# motor_controller.net
KiCad netlist of a schematic drawn in Altium Designer
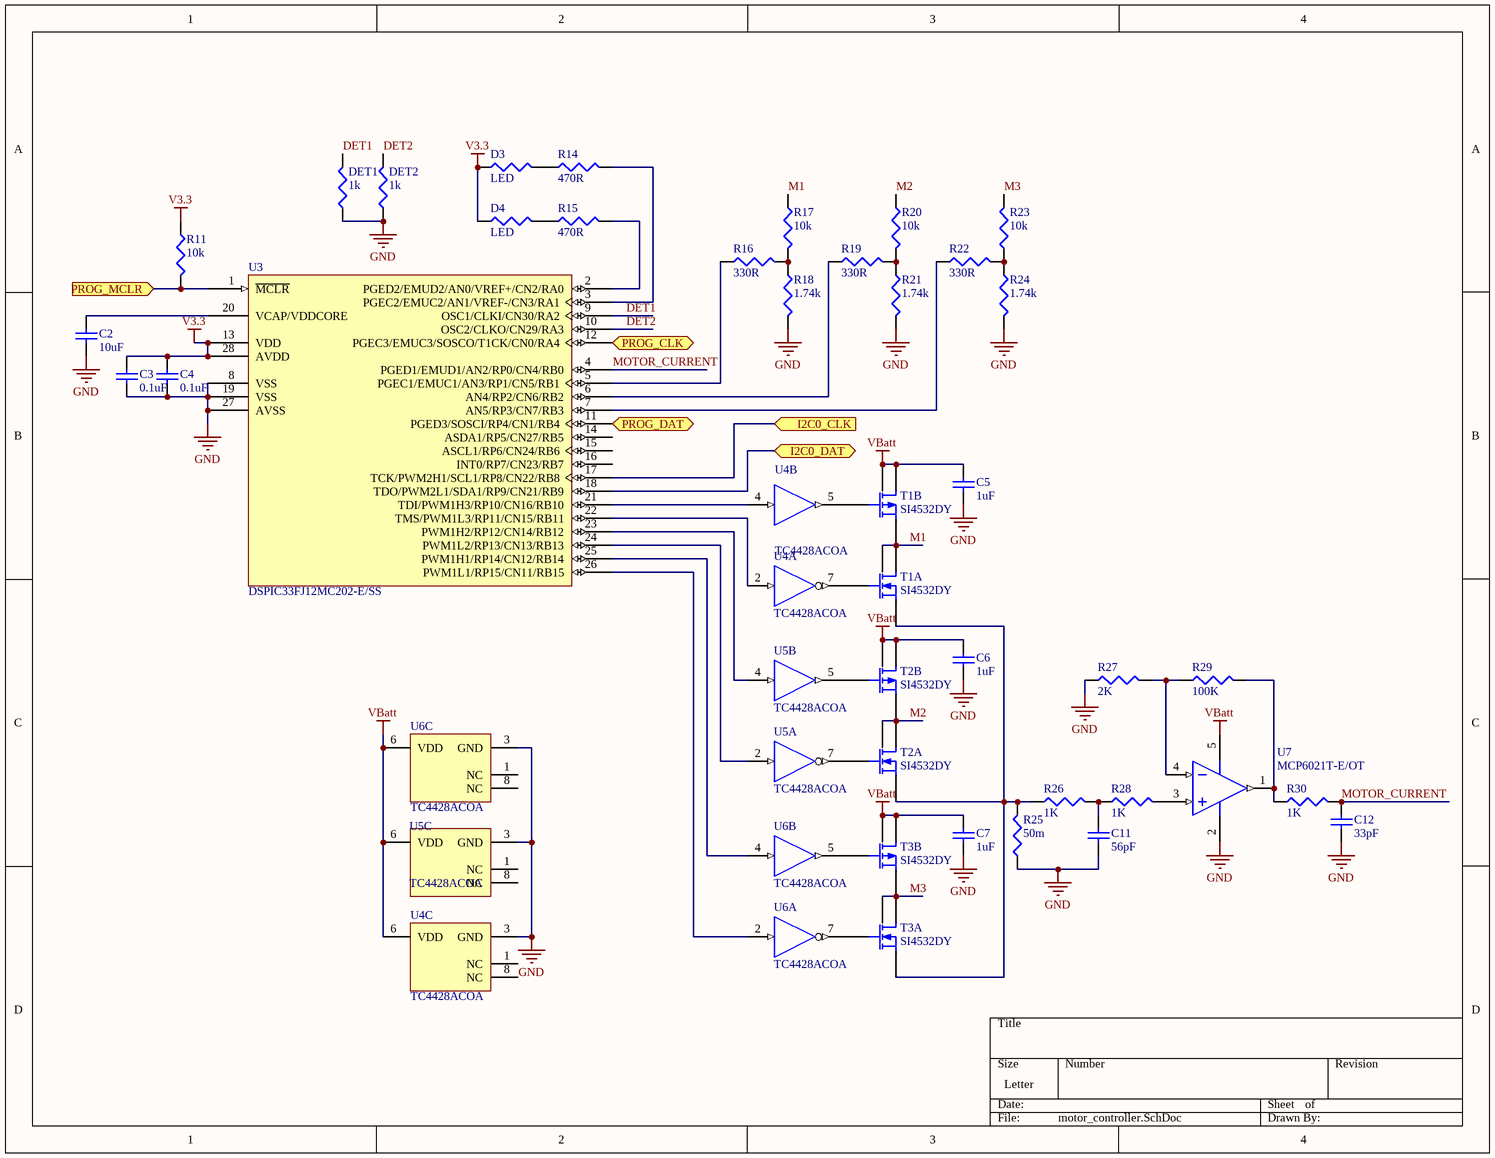
[diagram p0: motor_controller.SchDoc]

(export (version "E")
  (design (tool "Eeschema 10.0.6"))
  (components
    (comp (ref "C2")
      (value "10uF")
      (footprint "1608[0603]")
      (description "Capacitor (Semiconductor SIM Model)")
      (fields (field (name "PUBLISHER") "Altium Limited"))
      (libsource (lib "Miscellaneous Devices") (part "Cap Semi"))
    )
    (comp (ref "C3")
      (value "0.1uF")
      (footprint "1608[0603]")
      (description "Capacitor (Semiconductor SIM Model)")
      (fields (field (name "PUBLISHER") "Altium Limited"))
      (libsource (lib "Miscellaneous Devices") (part "Cap Semi"))
    )
    (comp (ref "C4")
      (value "0.1uF")
      (footprint "1608[0603]")
      (description "Capacitor (Semiconductor SIM Model)")
      (fields (field (name "PUBLISHER") "Altium Limited"))
      (libsource (lib "Miscellaneous Devices") (part "Cap Semi"))
    )
    (comp (ref "C5")
      (value "1uF")
      (footprint "1608[0603]")
      (description "Capacitor (Semiconductor SIM Model)")
      (fields (field (name "PUBLISHER") "Altium Limited"))
      (libsource (lib "Miscellaneous Devices") (part "Cap Semi"))
    )
    (comp (ref "C6")
      (value "1uF")
      (footprint "1608[0603]")
      (description "Capacitor (Semiconductor SIM Model)")
      (fields (field (name "PUBLISHER") "Altium Limited"))
      (libsource (lib "Miscellaneous Devices") (part "Cap Semi"))
    )
    (comp (ref "C7")
      (value "1uF")
      (footprint "1608[0603]")
      (description "Capacitor (Semiconductor SIM Model)")
      (fields (field (name "PUBLISHER") "Altium Limited"))
      (libsource (lib "Miscellaneous Devices") (part "Cap Semi"))
    )
    (comp (ref "C11")
      (value "56pF")
      (footprint "1608[0603]")
      (description "Capacitor (Semiconductor SIM Model)")
      (fields (field (name "PUBLISHER") "Altium Limited"))
      (libsource (lib "Miscellaneous Devices") (part "Cap Semi"))
    )
    (comp (ref "C12")
      (value "33pF")
      (footprint "1608[0603]")
      (description "Capacitor (Semiconductor SIM Model)")
      (fields (field (name "PUBLISHER") "Altium Limited"))
      (libsource (lib "Miscellaneous Devices") (part "Cap Semi"))
    )
    (comp (ref "D3")
      (value "LED")
      (footprint "J1-0603")
      (description "Resistor")
      (fields (field (name "PUBLISHER") "Altium Limited"))
      (libsource (lib "Miscellaneous Devices") (part "Res3"))
    )
    (comp (ref "D4")
      (value "LED")
      (footprint "J1-0603")
      (description "Resistor")
      (fields (field (name "PUBLISHER") "Altium Limited"))
      (libsource (lib "Miscellaneous Devices") (part "Res3"))
    )
    (comp (ref "DET1")
      (value "1k")
      (footprint "J1-0603")
      (description "Resistor")
      (fields (field (name "PUBLISHER") "Altium Limited"))
      (libsource (lib "Miscellaneous Devices") (part "Res3"))
    )
    (comp (ref "DET2")
      (value "1k")
      (footprint "J1-0603")
      (description "Resistor")
      (fields (field (name "PUBLISHER") "Altium Limited"))
      (libsource (lib "Miscellaneous Devices") (part "Res3"))
    )
    (comp (ref "R11")
      (value "10k")
      (footprint "J1-0603")
      (description "Resistor")
      (fields (field (name "PUBLISHER") "Altium Limited"))
      (libsource (lib "Miscellaneous Devices") (part "Res3"))
    )
    (comp (ref "R14")
      (value "470R")
      (footprint "J1-0603")
      (description "Resistor")
      (fields (field (name "PUBLISHER") "Altium Limited"))
      (libsource (lib "Miscellaneous Devices") (part "Res3"))
    )
    (comp (ref "R15")
      (value "470R")
      (footprint "J1-0603")
      (description "Resistor")
      (fields (field (name "PUBLISHER") "Altium Limited"))
      (libsource (lib "Miscellaneous Devices") (part "Res3"))
    )
    (comp (ref "R16")
      (value "330R")
      (footprint "J1-0603")
      (description "Resistor")
      (fields (field (name "PUBLISHER") "Altium Limited"))
      (libsource (lib "Miscellaneous Devices") (part "Res3"))
    )
    (comp (ref "R17")
      (value "10k")
      (footprint "J1-0603")
      (description "Resistor")
      (fields (field (name "PUBLISHER") "Altium Limited"))
      (libsource (lib "Miscellaneous Devices") (part "Res3"))
    )
    (comp (ref "R18")
      (value "1.74k")
      (footprint "J1-0603")
      (description "Resistor")
      (fields (field (name "PUBLISHER") "Altium Limited"))
      (libsource (lib "Miscellaneous Devices") (part "Res3"))
    )
    (comp (ref "R19")
      (value "330R")
      (footprint "J1-0603")
      (description "Resistor")
      (fields (field (name "PUBLISHER") "Altium Limited"))
      (libsource (lib "Miscellaneous Devices") (part "Res3"))
    )
    (comp (ref "R20")
      (value "10k")
      (footprint "J1-0603")
      (description "Resistor")
      (fields (field (name "PUBLISHER") "Altium Limited"))
      (libsource (lib "Miscellaneous Devices") (part "Res3"))
    )
    (comp (ref "R21")
      (value "1.74k")
      (footprint "J1-0603")
      (description "Resistor")
      (fields (field (name "PUBLISHER") "Altium Limited"))
      (libsource (lib "Miscellaneous Devices") (part "Res3"))
    )
    (comp (ref "R22")
      (value "330R")
      (footprint "J1-0603")
      (description "Resistor")
      (fields (field (name "PUBLISHER") "Altium Limited"))
      (libsource (lib "Miscellaneous Devices") (part "Res3"))
    )
    (comp (ref "R23")
      (value "10k")
      (footprint "J1-0603")
      (description "Resistor")
      (fields (field (name "PUBLISHER") "Altium Limited"))
      (libsource (lib "Miscellaneous Devices") (part "Res3"))
    )
    (comp (ref "R24")
      (value "1.74k")
      (footprint "J1-0603")
      (description "Resistor")
      (fields (field (name "PUBLISHER") "Altium Limited"))
      (libsource (lib "Miscellaneous Devices") (part "Res3"))
    )
    (comp (ref "R25")
      (value "50m")
      (footprint "14-1210")
      (description "Resistor")
      (fields (field (name "PUBLISHER") "Altium Limited"))
      (libsource (lib "Miscellaneous Devices") (part "Res3"))
    )
    (comp (ref "R26")
      (value "1K")
      (footprint "J1-0603")
      (description "Resistor")
      (fields (field (name "PUBLISHER") "Altium Limited"))
      (libsource (lib "Miscellaneous Devices") (part "Res3"))
    )
    (comp (ref "R27")
      (value "2K")
      (footprint "J1-0603")
      (description "Resistor")
      (fields (field (name "PUBLISHER") "Altium Limited"))
      (libsource (lib "Miscellaneous Devices") (part "Res3"))
    )
    (comp (ref "R28")
      (value "1K")
      (footprint "J1-0603")
      (description "Resistor")
      (fields (field (name "PUBLISHER") "Altium Limited"))
      (libsource (lib "Miscellaneous Devices") (part "Res3"))
    )
    (comp (ref "R29")
      (value "100K")
      (footprint "J1-0603")
      (description "Resistor")
      (fields (field (name "PUBLISHER") "Altium Limited"))
      (libsource (lib "Miscellaneous Devices") (part "Res3"))
    )
    (comp (ref "R30")
      (value "1K")
      (footprint "J1-0603")
      (description "Resistor")
      (fields (field (name "PUBLISHER") "Altium Limited"))
      (libsource (lib "Miscellaneous Devices") (part "Res3"))
    )
    (comp (ref "T1")
      (value "SI4532DY")
      (footprint "SOIC127P600-8L")
      (libsource (lib "custom_for_quadrotor") (part "SI4532DY"))
    )
    (comp (ref "T2")
      (value "SI4532DY")
      (footprint "SOIC127P600-8L")
      (libsource (lib "custom_for_quadrotor") (part "SI4532DY"))
    )
    (comp (ref "T3")
      (value "SI4532DY")
      (footprint "SOIC127P600-8L")
      (libsource (lib "custom_for_quadrotor") (part "SI4532DY"))
    )
    (comp (ref "U3")
      (value "DSPIC33FJ12MC202-E/SS")
      (footprint "SSOP-SS28_N")
      (libsource (lib "Microchip dsPIC33F") (part "DSPIC33FJ12MC202-E/SS"))
    )
    (comp (ref "U4")
      (value "TC4428ACOA")
      (footprint "SOIC-OA8_N")
      (description "1.5A Dual High-Speed Power MOSFET Driver, Complementary, Commercial Temperature")
      (libsource (lib "Microchip Power Management MOSFET Driver") (part "TC4428ACOA"))
    )
    (comp (ref "U5")
      (value "TC4428ACOA")
      (footprint "SOIC-OA8_N")
      (description "1.5A Dual High-Speed Power MOSFET Driver, Complementary, Commercial Temperature")
      (libsource (lib "Microchip Power Management MOSFET Driver") (part "TC4428ACOA"))
    )
    (comp (ref "U6")
      (value "TC4428ACOA")
      (footprint "SOIC-OA8_N")
      (description "1.5A Dual High-Speed Power MOSFET Driver, Complementary, Commercial Temperature")
      (libsource (lib "Microchip Power Management MOSFET Driver") (part "TC4428ACOA"))
    )
    (comp (ref "U7")
      (value "MCP6021T-E/OT")
      (footprint "SOT-23-OT5_N")
      (libsource (lib "Microchip Linear") (part "MCP6021T-E/OT"))
    )
  )
  (nets
    (net (code "1") (name "/DET1") (class "Default")
      (node (ref "DET1") (pin "2") (pinfunction "2_2") (pintype "passive"))
      (node (ref "U3") (pin "9") (pinfunction "OSC1/CLKI/CN30/RA2_9") (pintype "bidirectional"))
    )
    (net (code "2") (name "/DET2") (class "Default")
      (node (ref "DET2") (pin "2") (pinfunction "2_2") (pintype "passive"))
      (node (ref "U3") (pin "10") (pinfunction "OSC2/CLKO/CN29/RA3_10") (pintype "bidirectional"))
    )
    (net (code "3") (name "/I2C0_CLK") (class "Default")
      (node (ref "U3") (pin "17") (pinfunction "TCK/PWM2H1/SCL1/RP8/CN22/RB8_17") (pintype "bidirectional"))
    )
    (net (code "4") (name "/I2C0_DAT") (class "Default")
      (node (ref "U3") (pin "18") (pinfunction "TDO/PWM2L1/SDA1/RP9/CN21/RB9_18") (pintype "bidirectional"))
    )
    (net (code "5") (name "/M1") (class "Default")
      (node (ref "R17") (pin "1") (pinfunction "1_1") (pintype "passive"))
      (node (ref "T1") (pin "3") (pinfunction "S2_3") (pintype "passive"))
      (node (ref "T1") (pin "7") (pinfunction "D1_7") (pintype "passive"))
      (node (ref "T1") (pin "8") (pinfunction "D1_8") (pintype "passive"))
    )
    (net (code "6") (name "/M2") (class "Default")
      (node (ref "R20") (pin "1") (pinfunction "1_1") (pintype "passive"))
      (node (ref "T2") (pin "3") (pinfunction "S2_3") (pintype "passive"))
      (node (ref "T2") (pin "7") (pinfunction "D1_7") (pintype "passive"))
      (node (ref "T2") (pin "8") (pinfunction "D1_8") (pintype "passive"))
    )
    (net (code "7") (name "/M3") (class "Default")
      (node (ref "R23") (pin "2") (pinfunction "2_2") (pintype "passive"))
      (node (ref "T3") (pin "3") (pinfunction "S2_3") (pintype "passive"))
      (node (ref "T3") (pin "7") (pinfunction "D1_7") (pintype "passive"))
      (node (ref "T3") (pin "8") (pinfunction "D1_8") (pintype "passive"))
    )
    (net (code "8") (name "/MOTOR_CURRENT") (class "Default")
      (node (ref "C12") (pin "2") (pinfunction "2_2") (pintype "passive"))
      (node (ref "R30") (pin "2") (pinfunction "2_2") (pintype "passive"))
      (node (ref "U3") (pin "4") (pinfunction "PGED1/EMUD1/AN2/RP0/CN4/RB0_4") (pintype "bidirectional"))
    )
    (net (code "9") (name "/PROG_CLK") (class "Default")
      (node (ref "U3") (pin "12") (pinfunction "PGEC3/EMUC3/SOSCO/T1CK/CN0/RA4_12") (pintype "bidirectional"))
    )
    (net (code "10") (name "/PROG_DAT") (class "Default")
      (node (ref "U3") (pin "11") (pinfunction "PGED3/SOSCI/RP4/CN1/RB4_11") (pintype "bidirectional"))
    )
    (net (code "11") (name "/PROG_MCLR") (class "Default")
      (node (ref "R11") (pin "2") (pinfunction "2_2") (pintype "passive"))
      (node (ref "U3") (pin "1") (pinfunction "~{MCLR}_1") (pintype "input"))
    )
    (net (code "12") (name "GND") (class "Default")
      (node (ref "C11") (pin "1") (pinfunction "1_1") (pintype "passive"))
      (node (ref "C12") (pin "1") (pinfunction "1_1") (pintype "passive"))
      (node (ref "C2") (pin "1") (pinfunction "1_1") (pintype "passive"))
      (node (ref "C3") (pin "1") (pinfunction "1_1") (pintype "passive"))
      (node (ref "C4") (pin "1") (pinfunction "1_1") (pintype "passive"))
      (node (ref "C5") (pin "1") (pinfunction "1_1") (pintype "passive"))
      (node (ref "C6") (pin "1") (pinfunction "1_1") (pintype "passive"))
      (node (ref "C7") (pin "1") (pinfunction "1_1") (pintype "passive"))
      (node (ref "DET1") (pin "1") (pinfunction "1_1") (pintype "passive"))
      (node (ref "DET2") (pin "1") (pinfunction "1_1") (pintype "passive"))
      (node (ref "R18") (pin "2") (pinfunction "2_2") (pintype "passive"))
      (node (ref "R21") (pin "2") (pinfunction "2_2") (pintype "passive"))
      (node (ref "R24") (pin "2") (pinfunction "2_2") (pintype "passive"))
      (node (ref "R25") (pin "1") (pinfunction "1_1") (pintype "passive"))
      (node (ref "R27") (pin "1") (pinfunction "1_1") (pintype "passive"))
      (node (ref "U3") (pin "19") (pinfunction "VSS_19") (pintype "power_in"))
      (node (ref "U3") (pin "27") (pinfunction "AVSS_27") (pintype "power_in"))
      (node (ref "U3") (pin "8") (pinfunction "VSS_8") (pintype "power_in"))
      (node (ref "U4") (pin "3") (pinfunction "GND_3") (pintype "power_in"))
      (node (ref "U5") (pin "3") (pinfunction "GND_3") (pintype "power_in"))
      (node (ref "U6") (pin "3") (pinfunction "GND_3") (pintype "power_in"))
      (node (ref "U7") (pin "2") (pinfunction "VSS_2") (pintype "power_in"))
    )
    (net (code "13") (name "Net-(C11-Pad2)") (class "Default")
      (node (ref "C11") (pin "2") (pinfunction "2_2") (pintype "passive"))
      (node (ref "R26") (pin "2") (pinfunction "2_2") (pintype "passive"))
      (node (ref "R28") (pin "1") (pinfunction "1_1") (pintype "passive"))
    )
    (net (code "14") (name "Net-(D3-Pad2)") (class "Default")
      (node (ref "D3") (pin "2") (pinfunction "2_2") (pintype "passive"))
      (node (ref "R14") (pin "1") (pinfunction "1_1") (pintype "passive"))
    )
    (net (code "15") (name "Net-(D4-Pad2)") (class "Default")
      (node (ref "D4") (pin "2") (pinfunction "2_2") (pintype "passive"))
      (node (ref "R15") (pin "1") (pinfunction "1_1") (pintype "passive"))
    )
    (net (code "16") (name "Net-(R16-Pad2)") (class "Default")
      (node (ref "R16") (pin "2") (pinfunction "2_2") (pintype "passive"))
      (node (ref "R17") (pin "2") (pinfunction "2_2") (pintype "passive"))
      (node (ref "R18") (pin "1") (pinfunction "1_1") (pintype "passive"))
    )
    (net (code "17") (name "Net-(R19-Pad2)") (class "Default")
      (node (ref "R19") (pin "2") (pinfunction "2_2") (pintype "passive"))
      (node (ref "R20") (pin "2") (pinfunction "2_2") (pintype "passive"))
      (node (ref "R21") (pin "1") (pinfunction "1_1") (pintype "passive"))
    )
    (net (code "18") (name "Net-(R22-Pad2)") (class "Default")
      (node (ref "R22") (pin "2") (pinfunction "2_2") (pintype "passive"))
      (node (ref "R23") (pin "1") (pinfunction "1_1") (pintype "passive"))
      (node (ref "R24") (pin "1") (pinfunction "1_1") (pintype "passive"))
    )
    (net (code "19") (name "Net-(T1A-G1)") (class "Default")
      (node (ref "T1") (pin "2") (pinfunction "G1_2") (pintype "passive"))
      (node (ref "U4") (pin "7") (pinfunction "~{OUTA}_7") (pintype "output"))
    )
    (net (code "20") (name "Net-(T1A-S1)") (class "Default")
      (node (ref "R25") (pin "2") (pinfunction "2_2") (pintype "passive"))
      (node (ref "R26") (pin "1") (pinfunction "1_1") (pintype "passive"))
      (node (ref "T1") (pin "1") (pinfunction "S1_1") (pintype "passive"))
      (node (ref "T2") (pin "1") (pinfunction "S1_1") (pintype "passive"))
      (node (ref "T3") (pin "1") (pinfunction "S1_1") (pintype "passive"))
    )
    (net (code "21") (name "Net-(T1B-G2)") (class "Default")
      (node (ref "T1") (pin "4") (pinfunction "G2_4") (pintype "passive"))
      (node (ref "U4") (pin "5") (pinfunction "OUTB_5") (pintype "output"))
    )
    (net (code "22") (name "Net-(T2A-G1)") (class "Default")
      (node (ref "T2") (pin "2") (pinfunction "G1_2") (pintype "passive"))
      (node (ref "U5") (pin "7") (pinfunction "~{OUTA}_7") (pintype "output"))
    )
    (net (code "23") (name "Net-(T2B-G2)") (class "Default")
      (node (ref "T2") (pin "4") (pinfunction "G2_4") (pintype "passive"))
      (node (ref "U5") (pin "5") (pinfunction "OUTB_5") (pintype "output"))
    )
    (net (code "24") (name "Net-(T3A-G1)") (class "Default")
      (node (ref "T3") (pin "2") (pinfunction "G1_2") (pintype "passive"))
      (node (ref "U6") (pin "7") (pinfunction "~{OUTA}_7") (pintype "output"))
    )
    (net (code "25") (name "Net-(T3B-G2)") (class "Default")
      (node (ref "T3") (pin "4") (pinfunction "G2_4") (pintype "passive"))
      (node (ref "U6") (pin "5") (pinfunction "OUTB_5") (pintype "output"))
    )
    (net (code "26") (name "Net-(U3-AN4{slash}RP2{slash}CN6{slash}RB2)") (class "Default")
      (node (ref "R19") (pin "1") (pinfunction "1_1") (pintype "passive"))
      (node (ref "U3") (pin "6") (pinfunction "AN4/RP2/CN6/RB2_6") (pintype "bidirectional"))
    )
    (net (code "27") (name "Net-(U3-AN5{slash}RP3{slash}CN7{slash}RB3)") (class "Default")
      (node (ref "R22") (pin "1") (pinfunction "1_1") (pintype "passive"))
      (node (ref "U3") (pin "7") (pinfunction "AN5/RP3/CN7/RB3_7") (pintype "bidirectional"))
    )
    (net (code "28") (name "Net-(U3-PGEC1{slash}EMUC1{slash}AN3{slash}RP1{slash}CN5{slash}RB1)") (class "Default")
      (node (ref "R16") (pin "1") (pinfunction "1_1") (pintype "passive"))
      (node (ref "U3") (pin "5") (pinfunction "PGEC1/EMUC1/AN3/RP1/CN5/RB1_5") (pintype "bidirectional"))
    )
    (net (code "29") (name "Net-(U3-PGEC2{slash}EMUC2{slash}AN1{slash}VREF-{slash}CN3{slash}RA1)") (class "Default")
      (node (ref "R14") (pin "2") (pinfunction "2_2") (pintype "passive"))
      (node (ref "U3") (pin "3") (pinfunction "PGEC2/EMUC2/AN1/VREF-/CN3/RA1_3") (pintype "bidirectional"))
    )
    (net (code "30") (name "Net-(U3-PGED2{slash}EMUD2{slash}AN0{slash}VREF+{slash}CN2{slash}RA0)") (class "Default")
      (node (ref "R15") (pin "2") (pinfunction "2_2") (pintype "passive"))
      (node (ref "U3") (pin "2") (pinfunction "PGED2/EMUD2/AN0/VREF+/CN2/RA0_2") (pintype "bidirectional"))
    )
    (net (code "31") (name "Net-(U3-PWM1H1{slash}RP14{slash}CN12{slash}RB14)") (class "Default")
      (node (ref "U3") (pin "25") (pinfunction "PWM1H1/RP14/CN12/RB14_25") (pintype "bidirectional"))
      (node (ref "U6") (pin "4") (pinfunction "INB_4") (pintype "input"))
    )
    (net (code "32") (name "Net-(U3-PWM1H2{slash}RP12{slash}CN14{slash}RB12)") (class "Default")
      (node (ref "U3") (pin "23") (pinfunction "PWM1H2/RP12/CN14/RB12_23") (pintype "bidirectional"))
      (node (ref "U5") (pin "4") (pinfunction "INB_4") (pintype "input"))
    )
    (net (code "33") (name "Net-(U3-PWM1L1{slash}RP15{slash}CN11{slash}RB15)") (class "Default")
      (node (ref "U3") (pin "26") (pinfunction "PWM1L1/RP15/CN11/RB15_26") (pintype "bidirectional"))
      (node (ref "U6") (pin "2") (pinfunction "INA_2") (pintype "input"))
    )
    (net (code "34") (name "Net-(U3-PWM1L2{slash}RP13{slash}CN13{slash}RB13)") (class "Default")
      (node (ref "U3") (pin "24") (pinfunction "PWM1L2/RP13/CN13/RB13_24") (pintype "bidirectional"))
      (node (ref "U5") (pin "2") (pinfunction "INA_2") (pintype "input"))
    )
    (net (code "35") (name "Net-(U3-TDI{slash}PWM1H3{slash}RP10{slash}CN16{slash}RB10)") (class "Default")
      (node (ref "U3") (pin "21") (pinfunction "TDI/PWM1H3/RP10/CN16/RB10_21") (pintype "bidirectional"))
      (node (ref "U4") (pin "4") (pinfunction "INB_4") (pintype "input"))
    )
    (net (code "36") (name "Net-(U3-TMS{slash}PWM1L3{slash}RP11{slash}CN15{slash}RB11)") (class "Default")
      (node (ref "U3") (pin "22") (pinfunction "TMS/PWM1L3/RP11/CN15/RB11_22") (pintype "bidirectional"))
      (node (ref "U4") (pin "2") (pinfunction "INA_2") (pintype "input"))
    )
    (net (code "37") (name "Net-(U3-VCAP{slash}VDDCORE)") (class "Default")
      (node (ref "C2") (pin "2") (pinfunction "2_2") (pintype "passive"))
      (node (ref "U3") (pin "20") (pinfunction "VCAP/VDDCORE_20") (pintype "power_in"))
    )
    (net (code "38") (name "Net-(U7-VIN+)") (class "Default")
      (node (ref "R28") (pin "2") (pinfunction "2_2") (pintype "passive"))
      (node (ref "U7") (pin "3") (pinfunction "VIN+_3") (pintype "input"))
    )
    (net (code "39") (name "Net-(U7-VIN-)") (class "Default")
      (node (ref "R27") (pin "2") (pinfunction "2_2") (pintype "passive"))
      (node (ref "R29") (pin "1") (pinfunction "1_1") (pintype "passive"))
      (node (ref "U7") (pin "4") (pinfunction "VIN-_4") (pintype "input"))
    )
    (net (code "40") (name "Net-(U7-VOUT)") (class "Default")
      (node (ref "R29") (pin "2") (pinfunction "2_2") (pintype "passive"))
      (node (ref "R30") (pin "1") (pinfunction "1_1") (pintype "passive"))
      (node (ref "U7") (pin "1") (pinfunction "VOUT_1") (pintype "output"))
    )
    (net (code "41") (name "V3.3") (class "Default")
      (node (ref "C3") (pin "2") (pinfunction "2_2") (pintype "passive"))
      (node (ref "C4") (pin "2") (pinfunction "2_2") (pintype "passive"))
      (node (ref "D3") (pin "1") (pinfunction "1_1") (pintype "passive"))
      (node (ref "D4") (pin "1") (pinfunction "1_1") (pintype "passive"))
      (node (ref "R11") (pin "1") (pinfunction "1_1") (pintype "passive"))
      (node (ref "U3") (pin "13") (pinfunction "VDD_13") (pintype "power_in"))
      (node (ref "U3") (pin "28") (pinfunction "AVDD_28") (pintype "power_in"))
    )
    (net (code "42") (name "VBatt") (class "Default")
      (node (ref "C5") (pin "2") (pinfunction "2_2") (pintype "passive"))
      (node (ref "C6") (pin "2") (pinfunction "2_2") (pintype "passive"))
      (node (ref "C7") (pin "2") (pinfunction "2_2") (pintype "passive"))
      (node (ref "T1") (pin "5") (pinfunction "D2_5") (pintype "passive"))
      (node (ref "T1") (pin "6") (pinfunction "D2_6") (pintype "passive"))
      (node (ref "T2") (pin "5") (pinfunction "D2_5") (pintype "passive"))
      (node (ref "T2") (pin "6") (pinfunction "D2_6") (pintype "passive"))
      (node (ref "T3") (pin "5") (pinfunction "D2_5") (pintype "passive"))
      (node (ref "T3") (pin "6") (pinfunction "D2_6") (pintype "passive"))
      (node (ref "U4") (pin "6") (pinfunction "VDD_6") (pintype "power_in"))
      (node (ref "U5") (pin "6") (pinfunction "VDD_6") (pintype "power_in"))
      (node (ref "U6") (pin "6") (pinfunction "VDD_6") (pintype "power_in"))
      (node (ref "U7") (pin "5") (pinfunction "VDD_5") (pintype "power_in"))
    )
    (net (code "43") (name "unconnected-(U3-ASCL1{slash}RP6{slash}CN24{slash}RB6-Pad15)") (class "Default")
      (node (ref "U3") (pin "15") (pinfunction "ASCL1/RP6/CN24/RB6_15") (pintype "bidirectional"))
    )
    (net (code "44") (name "unconnected-(U3-ASDA1{slash}RP5{slash}CN27{slash}RB5-Pad14)") (class "Default")
      (node (ref "U3") (pin "14") (pinfunction "ASDA1/RP5/CN27/RB5_14") (pintype "bidirectional"))
    )
    (net (code "45") (name "unconnected-(U3-INT0{slash}RP7{slash}CN23{slash}RB7-Pad16)") (class "Default")
      (node (ref "U3") (pin "16") (pinfunction "INT0/RP7/CN23/RB7_16") (pintype "bidirectional"))
    )
    (net (code "46") (name "unconnected-(U4C-NC-Pad1)") (class "Default")
      (node (ref "U4") (pin "1") (pinfunction "NC_1") (pintype "passive"))
    )
    (net (code "47") (name "unconnected-(U4C-NC-Pad8)") (class "Default")
      (node (ref "U4") (pin "8") (pinfunction "NC_8") (pintype "passive"))
    )
    (net (code "48") (name "unconnected-(U5C-NC-Pad1)") (class "Default")
      (node (ref "U5") (pin "1") (pinfunction "NC_1") (pintype "passive"))
    )
    (net (code "49") (name "unconnected-(U5C-NC-Pad8)") (class "Default")
      (node (ref "U5") (pin "8") (pinfunction "NC_8") (pintype "passive"))
    )
    (net (code "50") (name "unconnected-(U6C-NC-Pad1)") (class "Default")
      (node (ref "U6") (pin "1") (pinfunction "NC_1") (pintype "passive"))
    )
    (net (code "51") (name "unconnected-(U6C-NC-Pad8)") (class "Default")
      (node (ref "U6") (pin "8") (pinfunction "NC_8") (pintype "passive"))
    )
  )
)
